# Display.net
KiCad netlist of a schematic drawn in EAGLE
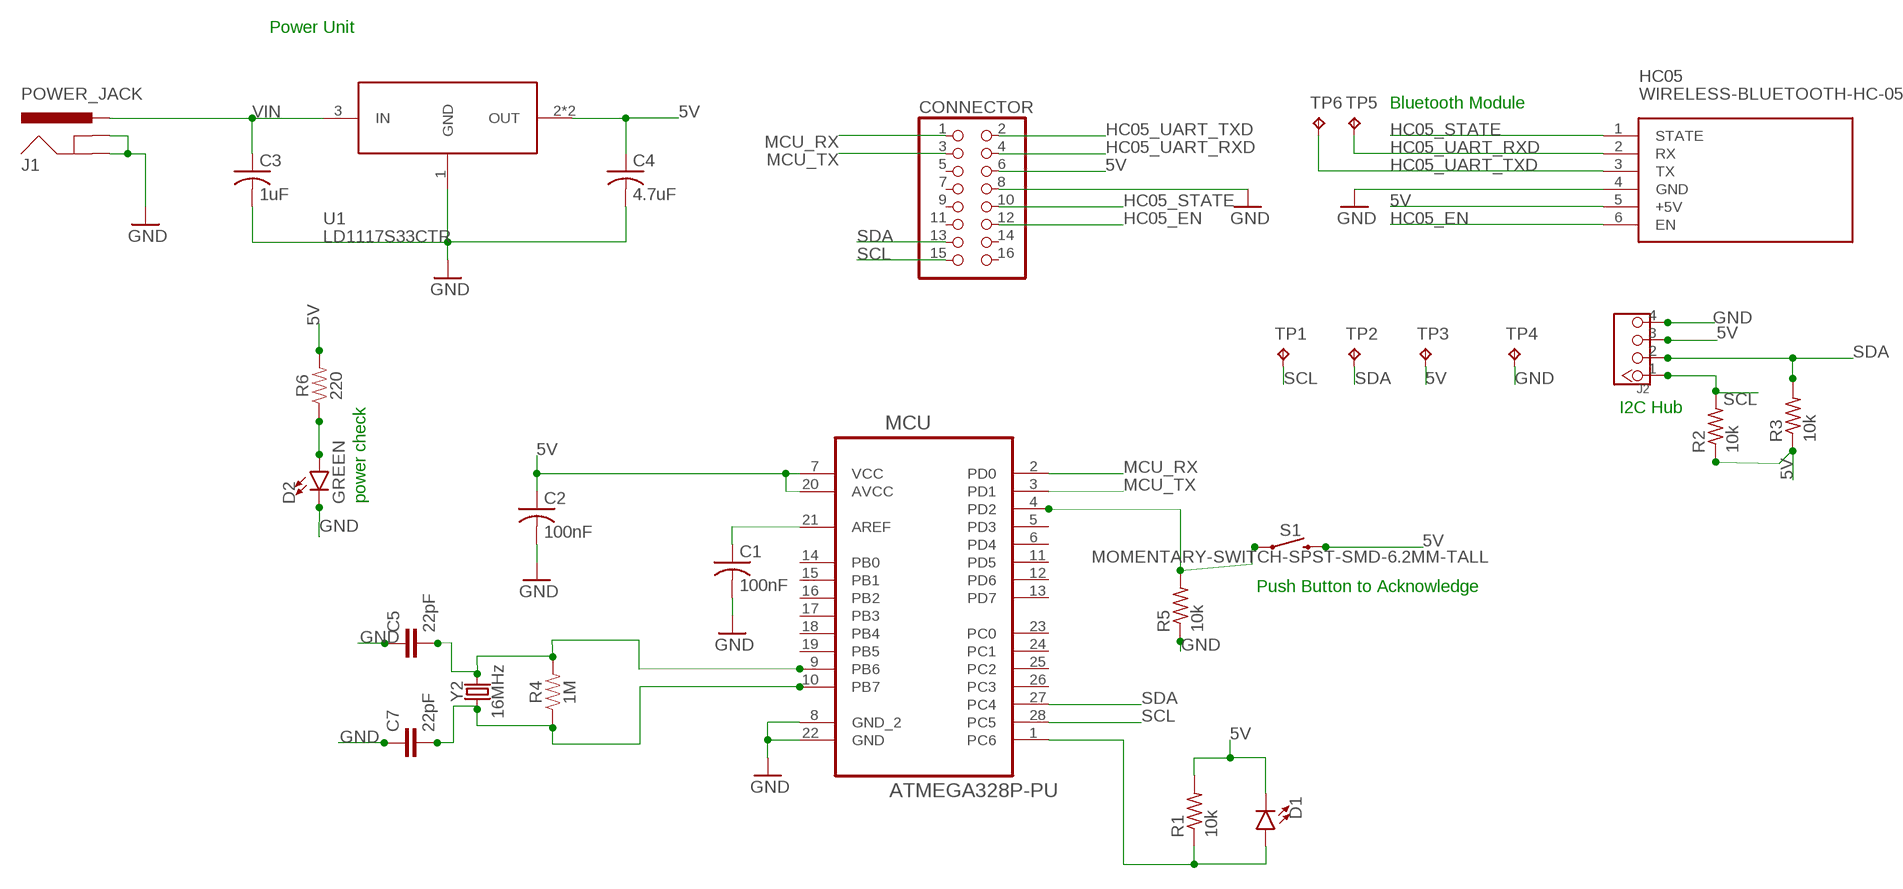
[diagram p0: schematic, sheet 1]

(export (version "E")
  (design (tool "Eeschema 10.0.6"))
  (components
    (comp (ref "C1")
      (value "100nF")
      (footprint "eagle-import:C0603")
      (libsource (lib "eagle-import") (part "C-USC0603"))
    )
    (comp (ref "C2")
      (value "100nF")
      (footprint "eagle-import:C0603")
      (libsource (lib "eagle-import") (part "C-USC0603"))
    )
    (comp (ref "C3")
      (value "1uF")
      (footprint "eagle-import:C0603")
      (libsource (lib "eagle-import") (part "C-USC0603"))
    )
    (comp (ref "C4")
      (value "4.7uF")
      (footprint "eagle-import:C0603")
      (libsource (lib "eagle-import") (part "C-USC0603"))
    )
    (comp (ref "C5")
      (value "22pF")
      (footprint "eagle-import:0603")
      (libsource (lib "eagle-import") (part "22PF-0603-50V-5%"))
    )
    (comp (ref "C7")
      (value "22pF")
      (footprint "eagle-import:0603")
      (libsource (lib "eagle-import") (part "22PF-0603-50V-5%"))
    )
    (comp (ref "CONNECTOR")
      (value "PINHD-2X8")
      (footprint "eagle-import:2X08")
      (libsource (lib "eagle-import") (part "PINHD-2X8"))
    )
    (comp (ref "D1")
      (value "LED1206")
      (footprint "eagle-import:LED-1206")
      (libsource (lib "eagle-import") (part "LED1206"))
    )
    (comp (ref "D2")
      (value "GREEN")
      (footprint "eagle-import:LED-1206")
      (libsource (lib "eagle-import") (part "LED-GREEN1206"))
    )
    (comp (ref "HC05")
      (value "WIRELESS-BLUETOOTH-HC-05")
      (footprint "eagle-import:WIRELESS-BLUETOOTH-HC-05")
      (libsource (lib "eagle-import") (part "WIRELESS-BLUETOOTH-HC-05"))
    )
    (comp (ref "J1")
      (value "POWER_JACK")
      (footprint "eagle-import:POWER_JACK_PTH")
      (libsource (lib "eagle-import") (part "POWER_JACK"))
    )
    (comp (ref "J2")
      (value "TWIG-4P-2.0")
      (footprint "eagle-import:4P-2.0-W_O-BUCKLE")
      (libsource (lib "eagle-import") (part "TWIG-4P-2.0"))
    )
    (comp (ref "MCU")
      (value "ATMEGA328P-PU")
      (footprint "eagle-import:DIP254P762X457-28")
      (libsource (lib "eagle-import") (part "ATMEGA328P-PU"))
    )
    (comp (ref "R1")
      (value "10k")
      (footprint "eagle-import:R0603")
      (libsource (lib "eagle-import") (part "R-US_R0603"))
    )
    (comp (ref "R2")
      (value "10k")
      (footprint "eagle-import:R0603")
      (libsource (lib "eagle-import") (part "R-US_R0603"))
    )
    (comp (ref "R3")
      (value "10k")
      (footprint "eagle-import:R0603")
      (libsource (lib "eagle-import") (part "R-US_R0603"))
    )
    (comp (ref "R4")
      (value "1M")
      (footprint "eagle-import:0603")
      (libsource (lib "eagle-import") (part "1MOHM-0603-1/4W-5%"))
    )
    (comp (ref "R5")
      (value "10k")
      (footprint "eagle-import:R0603")
      (libsource (lib "eagle-import") (part "R-US_R0603"))
    )
    (comp (ref "R6")
      (value "220")
      (footprint "eagle-import:0603")
      (libsource (lib "eagle-import") (part "220OHM-0603-1/10W-1%"))
    )
    (comp (ref "S1")
      (value "MOMENTARY-SWITCH-SPST-SMD-6.2MM-TALL")
      (footprint "eagle-import:TACTILE_SWITCH_SMD_6.2MM_TALL")
      (libsource (lib "eagle-import") (part "MOMENTARY-SWITCH-SPST-SMD-6.2MM-TALL"))
    )
    (comp (ref "TP1")
      (value "TPTP20R")
      (footprint "eagle-import:TP20R")
      (libsource (lib "eagle-import") (part "TPTP20R"))
    )
    (comp (ref "TP2")
      (value "TPTP20R")
      (footprint "eagle-import:TP20R")
      (libsource (lib "eagle-import") (part "TPTP20R"))
    )
    (comp (ref "TP3")
      (value "TPTP20R")
      (footprint "eagle-import:TP20R")
      (libsource (lib "eagle-import") (part "TPTP20R"))
    )
    (comp (ref "TP4")
      (value "TPTP20R")
      (footprint "eagle-import:TP20R")
      (libsource (lib "eagle-import") (part "TPTP20R"))
    )
    (comp (ref "TP5")
      (value "TPTP20R")
      (footprint "eagle-import:TP20R")
      (libsource (lib "eagle-import") (part "TPTP20R"))
    )
    (comp (ref "TP6")
      (value "TPTP20R")
      (footprint "eagle-import:TP20R")
      (libsource (lib "eagle-import") (part "TPTP20R"))
    )
    (comp (ref "U1")
      (value "LD1117S33CTR")
      (footprint "eagle-import:SOT223")
      (fields (field (name "MF") "STMicroelectronics"))
      (libsource (lib "eagle-import") (part "LD1117S33CTR"))
    )
    (comp (ref "Y2")
      (value "16MHz")
      (footprint "eagle-import:HC49US")
      (libsource (lib "eagle-import") (part "CRYSTAL-16MHZPTH-HC49US"))
    )
  )
  (nets
    (net (code "1") (name "/5V") (class "Default")
      (node (ref "C2") (pin "1") (pinfunction "1_1") (pintype "passive"))
      (node (ref "C4") (pin "1") (pinfunction "1_1") (pintype "passive"))
      (node (ref "CONNECTOR") (pin "6") (pinfunction "6_6") (pintype "passive"))
      (node (ref "D1") (pin "C") (pinfunction "C_C") (pintype "passive"))
      (node (ref "HC05") (pin "5") (pinfunction "+5V_5") (pintype "power_in"))
      (node (ref "J2") (pin "3") (pinfunction "3_3") (pintype "bidirectional"))
      (node (ref "MCU") (pin "20") (pinfunction "AVCC_20") (pintype "power_in"))
      (node (ref "MCU") (pin "7") (pinfunction "VCC_7") (pintype "power_in"))
      (node (ref "R1") (pin "2") (pinfunction "2_2") (pintype "passive"))
      (node (ref "R2") (pin "1") (pinfunction "1_1") (pintype "passive"))
      (node (ref "R3") (pin "1") (pinfunction "1_1") (pintype "passive"))
      (node (ref "R6") (pin "2") (pinfunction "2_2") (pintype "passive"))
      (node (ref "S1") (pin "B2") (pinfunction "2_B2") (pintype "passive"))
      (node (ref "TP3") (pin "TP") (pinfunction "TP_TP") (pintype "input"))
      (node (ref "U1") (pin "2") (pinfunction "OUT_2") (pintype "output"))
      (node (ref "U1") (pin "4") (pinfunction "OUT_4") (pintype "output"))
    )
    (net (code "2") (name "/HC05_EN") (class "Default")
      (node (ref "CONNECTOR") (pin "12") (pinfunction "12_12") (pintype "passive"))
      (node (ref "HC05") (pin "6") (pinfunction "EN_6") (pintype "bidirectional"))
    )
    (net (code "3") (name "/HC05_STATE") (class "Default")
      (node (ref "CONNECTOR") (pin "10") (pinfunction "10_10") (pintype "passive"))
      (node (ref "HC05") (pin "1") (pinfunction "STATE_1") (pintype "bidirectional"))
    )
    (net (code "4") (name "/HC05_UART_RXD") (class "Default")
      (node (ref "CONNECTOR") (pin "4") (pinfunction "4_4") (pintype "passive"))
      (node (ref "HC05") (pin "2") (pinfunction "RX_2") (pintype "bidirectional"))
      (node (ref "TP5") (pin "TP") (pinfunction "TP_TP") (pintype "input"))
    )
    (net (code "5") (name "/HC05_UART_TXD") (class "Default")
      (node (ref "CONNECTOR") (pin "2") (pinfunction "2_2") (pintype "passive"))
      (node (ref "HC05") (pin "3") (pinfunction "TX_3") (pintype "bidirectional"))
      (node (ref "TP6") (pin "TP") (pinfunction "TP_TP") (pintype "input"))
    )
    (net (code "6") (name "/MCU_RX") (class "Default")
      (node (ref "CONNECTOR") (pin "1") (pinfunction "1_1") (pintype "passive"))
      (node (ref "MCU") (pin "2") (pinfunction "PD0_2") (pintype "bidirectional"))
    )
    (net (code "7") (name "/MCU_TX") (class "Default")
      (node (ref "CONNECTOR") (pin "3") (pinfunction "3_3") (pintype "passive"))
      (node (ref "MCU") (pin "3") (pinfunction "PD1_3") (pintype "bidirectional"))
    )
    (net (code "8") (name "/SCL") (class "Default")
      (node (ref "CONNECTOR") (pin "15") (pinfunction "15_15") (pintype "passive"))
      (node (ref "J2") (pin "1") (pinfunction "1_1") (pintype "bidirectional"))
      (node (ref "MCU") (pin "28") (pinfunction "PC5_28") (pintype "bidirectional"))
      (node (ref "R2") (pin "2") (pinfunction "2_2") (pintype "passive"))
      (node (ref "TP1") (pin "TP") (pinfunction "TP_TP") (pintype "input"))
    )
    (net (code "9") (name "/SDA") (class "Default")
      (node (ref "CONNECTOR") (pin "13") (pinfunction "13_13") (pintype "passive"))
      (node (ref "J2") (pin "2") (pinfunction "2_2") (pintype "bidirectional"))
      (node (ref "MCU") (pin "27") (pinfunction "PC4_27") (pintype "bidirectional"))
      (node (ref "R3") (pin "2") (pinfunction "2_2") (pintype "passive"))
      (node (ref "TP2") (pin "TP") (pinfunction "TP_TP") (pintype "input"))
    )
    (net (code "10") (name "/VIN") (class "Default")
      (node (ref "C3") (pin "1") (pinfunction "1_1") (pintype "passive"))
      (node (ref "J1") (pin "PWR") (pinfunction "PWR_PWR") (pintype "bidirectional"))
      (node (ref "U1") (pin "3") (pinfunction "IN_3") (pintype "input"))
    )
    (net (code "11") (name "GND") (class "Default")
      (node (ref "C1") (pin "2") (pinfunction "2_2") (pintype "passive"))
      (node (ref "C2") (pin "2") (pinfunction "2_2") (pintype "passive"))
      (node (ref "C3") (pin "2") (pinfunction "2_2") (pintype "passive"))
      (node (ref "C4") (pin "2") (pinfunction "2_2") (pintype "passive"))
      (node (ref "C5") (pin "1") (pinfunction "1_1") (pintype "passive"))
      (node (ref "C7") (pin "1") (pinfunction "1_1") (pintype "passive"))
      (node (ref "CONNECTOR") (pin "8") (pinfunction "8_8") (pintype "passive"))
      (node (ref "D2") (pin "C") (pinfunction "C_C") (pintype "passive"))
      (node (ref "HC05") (pin "4") (pinfunction "GND_4") (pintype "power_in"))
      (node (ref "J1") (pin "GND") (pinfunction "GND_GND") (pintype "bidirectional"))
      (node (ref "J1") (pin "GNDBREAK") (pinfunction "GNDBREAK_GNDBREAK") (pintype "bidirectional"))
      (node (ref "J2") (pin "4") (pinfunction "4_4") (pintype "bidirectional"))
      (node (ref "MCU") (pin "22") (pinfunction "GND_22") (pintype "passive"))
      (node (ref "MCU") (pin "8") (pinfunction "GND_2_8") (pintype "passive"))
      (node (ref "R5") (pin "1") (pinfunction "1_1") (pintype "passive"))
      (node (ref "TP4") (pin "TP") (pinfunction "TP_TP") (pintype "input"))
      (node (ref "U1") (pin "1") (pinfunction "GND_1") (pintype "passive"))
    )
    (net (code "12") (name "Net-(D2-PadA)") (class "Default")
      (node (ref "D2") (pin "A") (pinfunction "A_A") (pintype "passive"))
      (node (ref "R6") (pin "1") (pinfunction "1_1") (pintype "passive"))
    )
    (net (code "13") (name "Net-(MCU-AREF)") (class "Default")
      (node (ref "C1") (pin "1") (pinfunction "1_1") (pintype "passive"))
      (node (ref "MCU") (pin "21") (pinfunction "AREF_21") (pintype "input"))
    )
    (net (code "14") (name "Net-(MCU-PB6)") (class "Default")
      (node (ref "C5") (pin "2") (pinfunction "2_2") (pintype "passive"))
      (node (ref "MCU") (pin "9") (pinfunction "PB6_9") (pintype "bidirectional"))
      (node (ref "R4") (pin "2") (pinfunction "2_2") (pintype "passive"))
      (node (ref "Y2") (pin "2") (pinfunction "2_2") (pintype "passive"))
    )
    (net (code "15") (name "Net-(MCU-PB7)") (class "Default")
      (node (ref "C7") (pin "2") (pinfunction "2_2") (pintype "passive"))
      (node (ref "MCU") (pin "10") (pinfunction "PB7_10") (pintype "bidirectional"))
      (node (ref "R4") (pin "1") (pinfunction "1_1") (pintype "passive"))
      (node (ref "Y2") (pin "1") (pinfunction "1_1") (pintype "passive"))
    )
    (net (code "16") (name "Net-(MCU-PC6)") (class "Default")
      (node (ref "D1") (pin "A") (pinfunction "A_A") (pintype "passive"))
      (node (ref "MCU") (pin "1") (pinfunction "PC6_1") (pintype "bidirectional"))
      (node (ref "R1") (pin "1") (pinfunction "1_1") (pintype "passive"))
    )
    (net (code "17") (name "Net-(MCU-PD2)") (class "Default")
      (node (ref "MCU") (pin "4") (pinfunction "PD2_4") (pintype "bidirectional"))
      (node (ref "R5") (pin "2") (pinfunction "2_2") (pintype "passive"))
      (node (ref "S1") (pin "A2") (pinfunction "1_A2") (pintype "passive"))
    )
    (net (code "18") (name "unconnected-(CONNECTOR-Pad5)") (class "Default")
      (node (ref "CONNECTOR") (pin "5") (pinfunction "5_5") (pintype "passive"))
    )
    (net (code "19") (name "unconnected-(CONNECTOR-Pad7)") (class "Default")
      (node (ref "CONNECTOR") (pin "7") (pinfunction "7_7") (pintype "passive"))
    )
    (net (code "20") (name "unconnected-(CONNECTOR-Pad9)") (class "Default")
      (node (ref "CONNECTOR") (pin "9") (pinfunction "9_9") (pintype "passive"))
    )
    (net (code "21") (name "unconnected-(CONNECTOR-Pad11)") (class "Default")
      (node (ref "CONNECTOR") (pin "11") (pinfunction "11_11") (pintype "passive"))
    )
    (net (code "22") (name "unconnected-(CONNECTOR-Pad14)") (class "Default")
      (node (ref "CONNECTOR") (pin "14") (pinfunction "14_14") (pintype "passive"))
    )
    (net (code "23") (name "unconnected-(CONNECTOR-Pad16)") (class "Default")
      (node (ref "CONNECTOR") (pin "16") (pinfunction "16_16") (pintype "passive"))
    )
    (net (code "24") (name "unconnected-(MCU-PB0-Pad14)") (class "Default")
      (node (ref "MCU") (pin "14") (pinfunction "PB0_14") (pintype "bidirectional"))
    )
    (net (code "25") (name "unconnected-(MCU-PB1-Pad15)") (class "Default")
      (node (ref "MCU") (pin "15") (pinfunction "PB1_15") (pintype "bidirectional"))
    )
    (net (code "26") (name "unconnected-(MCU-PB2-Pad16)") (class "Default")
      (node (ref "MCU") (pin "16") (pinfunction "PB2_16") (pintype "bidirectional"))
    )
    (net (code "27") (name "unconnected-(MCU-PB3-Pad17)") (class "Default")
      (node (ref "MCU") (pin "17") (pinfunction "PB3_17") (pintype "bidirectional"))
    )
    (net (code "28") (name "unconnected-(MCU-PB4-Pad18)") (class "Default")
      (node (ref "MCU") (pin "18") (pinfunction "PB4_18") (pintype "bidirectional"))
    )
    (net (code "29") (name "unconnected-(MCU-PB5-Pad19)") (class "Default")
      (node (ref "MCU") (pin "19") (pinfunction "PB5_19") (pintype "bidirectional"))
    )
    (net (code "30") (name "unconnected-(MCU-PC0-Pad23)") (class "Default")
      (node (ref "MCU") (pin "23") (pinfunction "PC0_23") (pintype "bidirectional"))
    )
    (net (code "31") (name "unconnected-(MCU-PC1-Pad24)") (class "Default")
      (node (ref "MCU") (pin "24") (pinfunction "PC1_24") (pintype "bidirectional"))
    )
    (net (code "32") (name "unconnected-(MCU-PC2-Pad25)") (class "Default")
      (node (ref "MCU") (pin "25") (pinfunction "PC2_25") (pintype "bidirectional"))
    )
    (net (code "33") (name "unconnected-(MCU-PC3-Pad26)") (class "Default")
      (node (ref "MCU") (pin "26") (pinfunction "PC3_26") (pintype "bidirectional"))
    )
    (net (code "34") (name "unconnected-(MCU-PD3-Pad5)") (class "Default")
      (node (ref "MCU") (pin "5") (pinfunction "PD3_5") (pintype "bidirectional"))
    )
    (net (code "35") (name "unconnected-(MCU-PD4-Pad6)") (class "Default")
      (node (ref "MCU") (pin "6") (pinfunction "PD4_6") (pintype "bidirectional"))
    )
    (net (code "36") (name "unconnected-(MCU-PD5-Pad11)") (class "Default")
      (node (ref "MCU") (pin "11") (pinfunction "PD5_11") (pintype "bidirectional"))
    )
    (net (code "37") (name "unconnected-(MCU-PD6-Pad12)") (class "Default")
      (node (ref "MCU") (pin "12") (pinfunction "PD6_12") (pintype "bidirectional"))
    )
    (net (code "38") (name "unconnected-(MCU-PD7-Pad13)") (class "Default")
      (node (ref "MCU") (pin "13") (pinfunction "PD7_13") (pintype "bidirectional"))
    )
  )
)
